# Buttons.net
KiCad netlist of a schematic drawn in Altium Designer
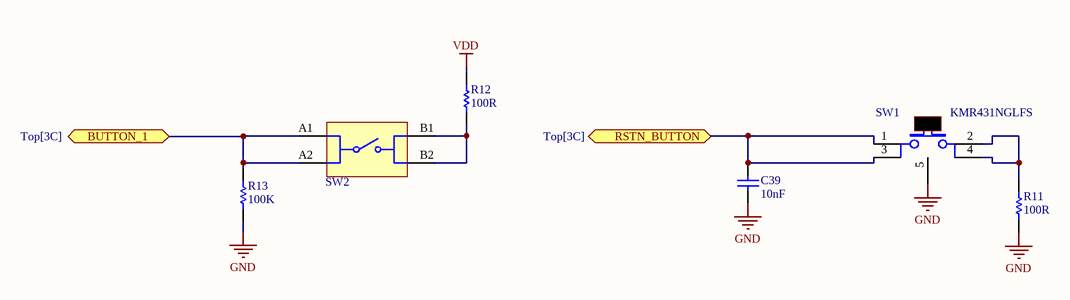
[diagram p0: Buttons.SchDoc]

(export (version "E")
  (design (tool "Eeschema 10.0.6"))
  (components
    (comp (ref "C39")
      (value "10nF")
      (footprint "C0402")
      (description "Capacitor, MLCC, 10nF, 16V, X7R, +/-10%, 0402, T=0.5mm")
      (fields (field (name "INTERNAL_PART_NUMBER") "MCD-00011") (field (name "MANUFACTURER") "YAGEO"))
      (libsource (lib "MCD_PARTS_database") (part "Capacitor"))
    )
    (comp (ref "R11")
      (value "100R")
      (footprint "R0402")
      (description "Resistor, 100R, 0402, +/-0.1%, 1/16W, +/-25ppm/°C")
      (fields (field (name "INTERNAL_PART_NUMBER") "MCD-02655") (field (name "MANUFACTURER") "YAGEO"))
      (libsource (lib "MCD_PARTS_database") (part "Resistor"))
    )
    (comp (ref "R12")
      (value "100R")
      (footprint "R0402")
      (description "Resistor, 100R, 0402, +/-0.1%, 1/16W, +/-25ppm/°C")
      (fields (field (name "INTERNAL_PART_NUMBER") "MCD-02655") (field (name "MANUFACTURER") "YAGEO"))
      (libsource (lib "MCD_PARTS_database") (part "Resistor"))
    )
    (comp (ref "R13")
      (value "100K")
      (footprint "R0402")
      (description "Resistor, 100K, 0402, +/-1%, 1/16W")
      (fields (field (name "INTERNAL_PART_NUMBER") "MCD-00059") (field (name "MANUFACTURER") "YAGEO"))
      (libsource (lib "MCD_PARTS_database") (part "Resistor"))
    )
    (comp (ref "SW1")
      (value "KMR431NGLFS")
      (footprint "SWI_C&K_Y78B23110FP__ITT_KMR231GLFS")
      (description "Switch tactile, SPST-NO, 32V, 50mA, 2.8x4.6mm")
      (fields (field (name "INTERNAL_PART_NUMBER") "MCD-00715") (field (name "MANUFACTURER") "C&K"))
      (libsource (lib "MCD_PARTS_database") (part "SW-PUSH-CMS_BLACK_PIN1-3_2-4"))
    )
    (comp (ref "SW2")
      (value "434351045816")
      (footprint "434351045816")
      (description "WS-TASU SMT Tact Switch 4.7x3.5mm side push, SPST-NO, 12VDC, 50mA, 160g")
      (fields (field (name "MANUFACTURER") "Wurth Elektronik"))
      (libsource (lib "missing_parts") (part "434351045816"))
    )
  )
  (nets
    (net (code "1") (name "/BUTTON_1") (class "Default")
      (node (ref "R13") (pin "2") (pinfunction "2_2") (pintype "passive"))
      (node (ref "SW2") (pin "A1") (pinfunction "A1_A1") (pintype "passive"))
      (node (ref "SW2") (pin "A2") (pinfunction "A2_A2") (pintype "passive"))
    )
    (net (code "2") (name "/RSTN_BUTTON") (class "Default")
      (node (ref "C39") (pin "2") (pinfunction "2_2") (pintype "passive"))
      (node (ref "SW1") (pin "1") (pinfunction "1_1") (pintype "passive"))
      (node (ref "SW1") (pin "3") (pinfunction "3_3") (pintype "passive"))
    )
    (net (code "3") (name "GND") (class "Default")
      (node (ref "C39") (pin "1") (pinfunction "1_1") (pintype "passive"))
      (node (ref "R11") (pin "1") (pinfunction "1_1") (pintype "passive"))
      (node (ref "R13") (pin "1") (pinfunction "1_1") (pintype "passive"))
      (node (ref "SW1") (pin "5") (pinfunction "GND_5") (pintype "passive"))
    )
    (net (code "4") (name "Net-(R11-Pad2)") (class "Default")
      (node (ref "R11") (pin "2") (pinfunction "2_2") (pintype "passive"))
      (node (ref "SW1") (pin "2") (pinfunction "2_2") (pintype "passive"))
      (node (ref "SW1") (pin "4") (pinfunction "4_4") (pintype "passive"))
    )
    (net (code "5") (name "Net-(R12-Pad1)") (class "Default")
      (node (ref "R12") (pin "1") (pinfunction "1_1") (pintype "passive"))
      (node (ref "SW2") (pin "B1") (pinfunction "B1_B1") (pintype "passive"))
      (node (ref "SW2") (pin "B2") (pinfunction "B2_B2") (pintype "passive"))
    )
    (net (code "6") (name "VDD") (class "Default")
      (node (ref "R12") (pin "2") (pinfunction "2_2") (pintype "passive"))
    )
  )
)
